# zxuno.net
KiCad netlist of a schematic drawn in EAGLE
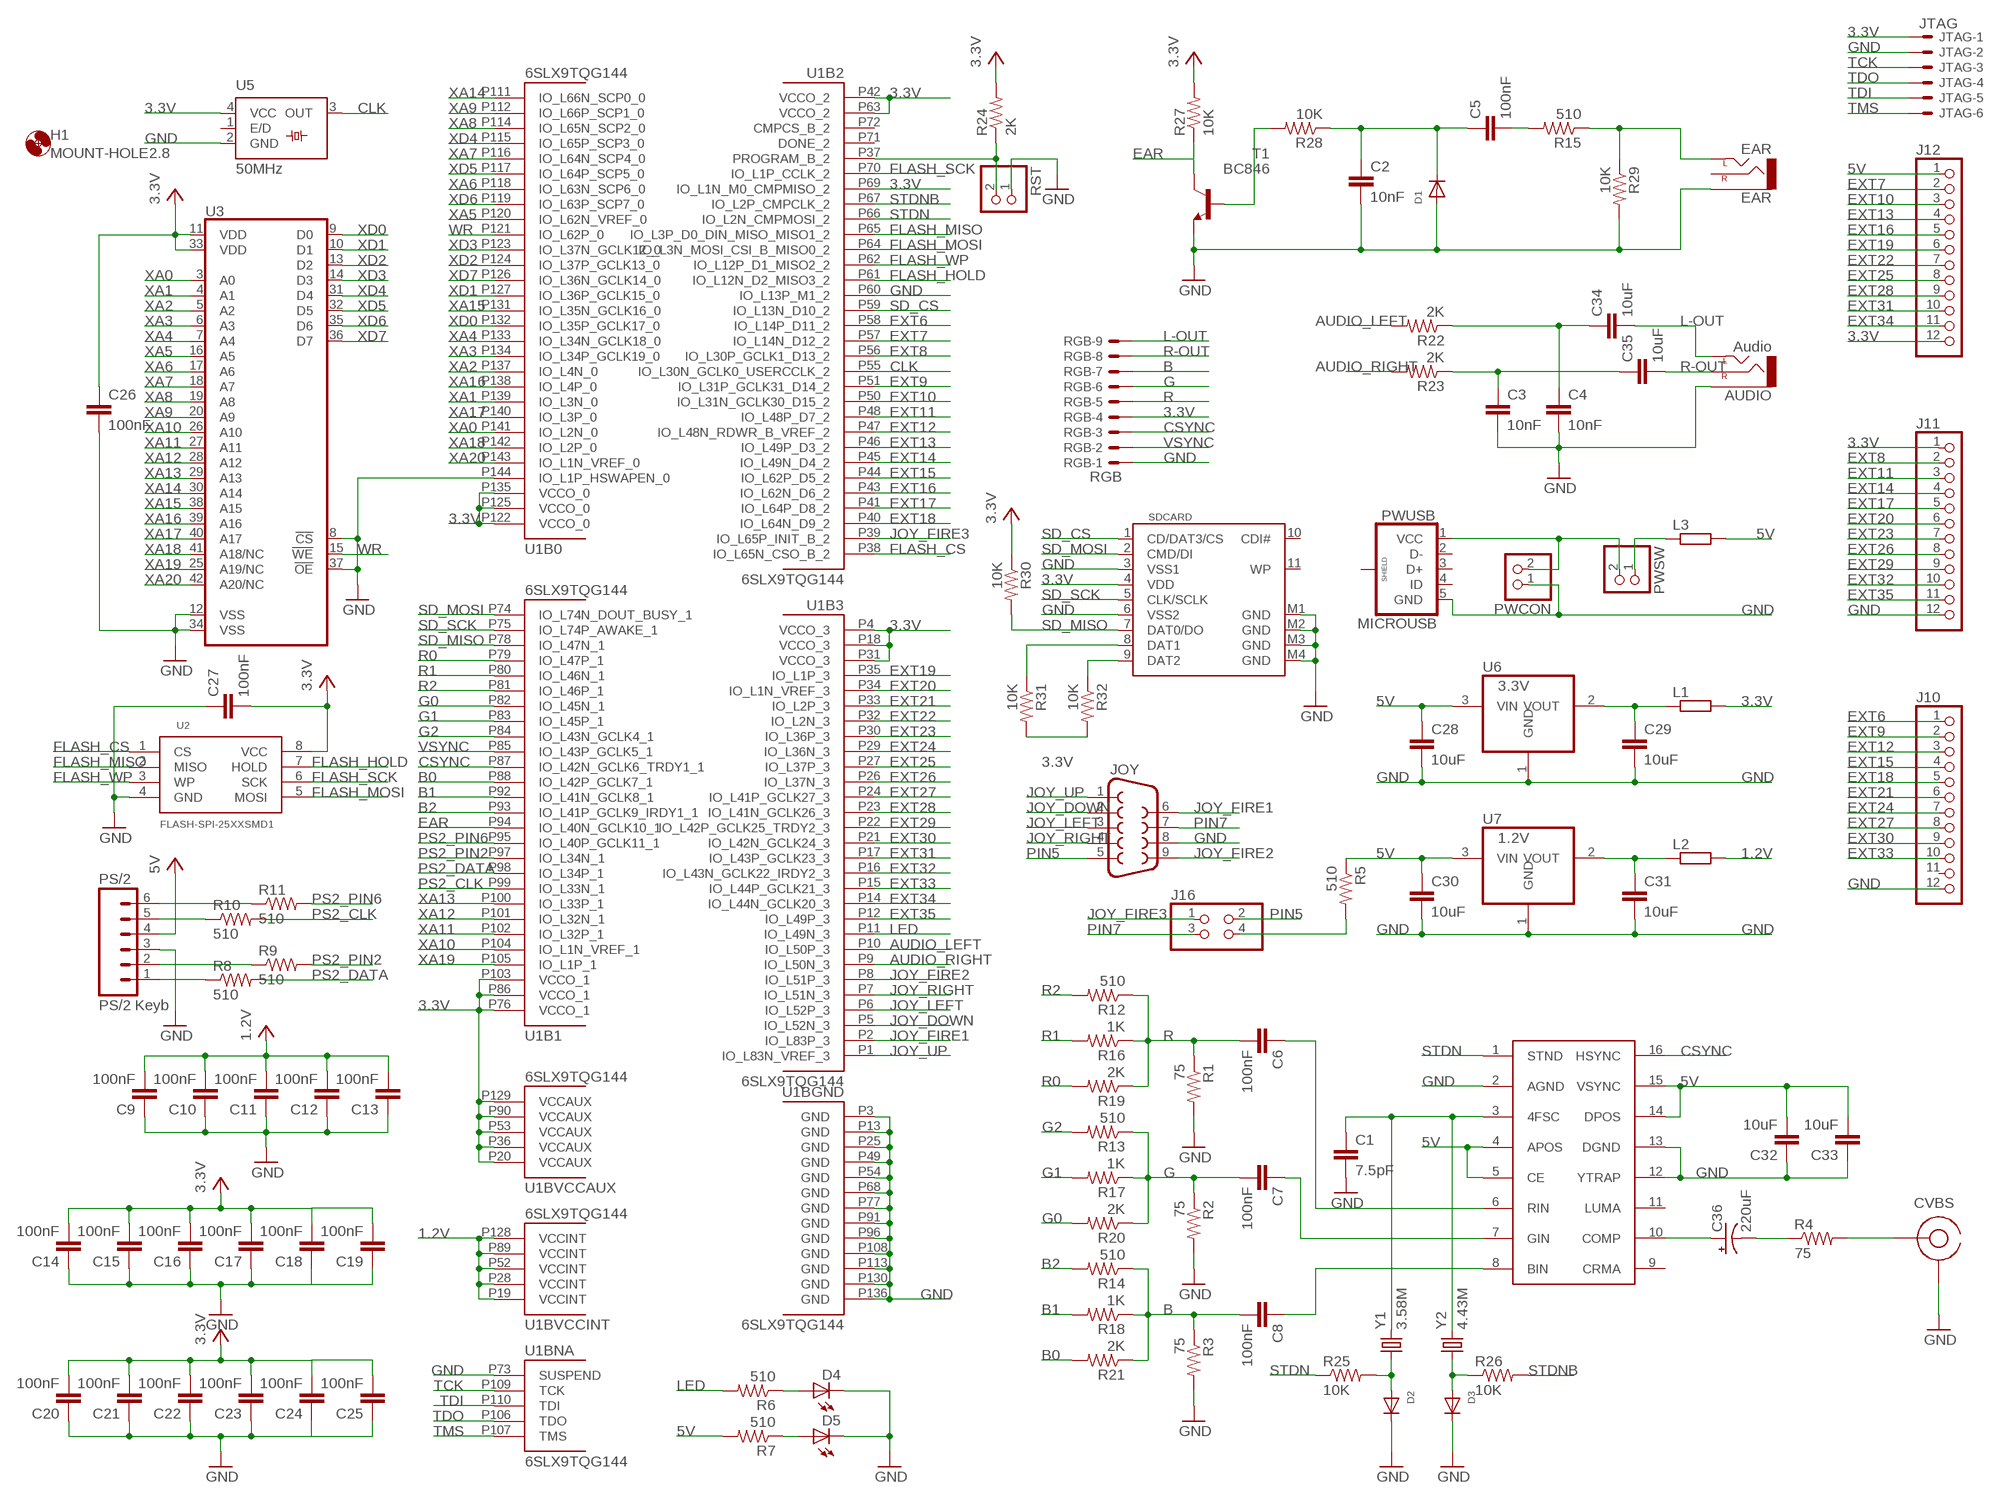
[diagram p0: schematic, sheet 1]

(export (version "E")
  (design (tool "Eeschema 10.0.6"))
  (components
    (comp (ref "AUDIO")
      (value "Audio")
      (footprint "eagle-import:AUDIO-JACK")
      (libsource (lib "eagle-import") (part "AUDIO-JACKPTH"))
    )
    (comp (ref "C1")
      (value "7.5pF")
      (footprint "eagle-import:C0805")
      (libsource (lib "eagle-import") (part "C-EUC0805"))
    )
    (comp (ref "C2")
      (value "10nF")
      (footprint "eagle-import:C0805")
      (libsource (lib "eagle-import") (part "C-EUC0805"))
    )
    (comp (ref "C3")
      (value "10nF")
      (footprint "eagle-import:C0805")
      (libsource (lib "eagle-import") (part "C-EUC0805"))
    )
    (comp (ref "C4")
      (value "10nF")
      (footprint "eagle-import:C0805")
      (libsource (lib "eagle-import") (part "C-EUC0805"))
    )
    (comp (ref "C5")
      (value "100nF")
      (footprint "eagle-import:C0603")
      (libsource (lib "eagle-import") (part "C-EUC0603"))
    )
    (comp (ref "C6")
      (value "100nF")
      (footprint "eagle-import:C0603")
      (libsource (lib "eagle-import") (part "C-EUC0603"))
    )
    (comp (ref "C7")
      (value "100nF")
      (footprint "eagle-import:C0603")
      (libsource (lib "eagle-import") (part "C-EUC0603"))
    )
    (comp (ref "C8")
      (value "100nF")
      (footprint "eagle-import:C0603")
      (libsource (lib "eagle-import") (part "C-EUC0603"))
    )
    (comp (ref "C9")
      (value "100nF")
      (footprint "eagle-import:C0603")
      (libsource (lib "eagle-import") (part "C-EUC0603"))
    )
    (comp (ref "C10")
      (value "100nF")
      (footprint "eagle-import:C0603")
      (libsource (lib "eagle-import") (part "C-EUC0603"))
    )
    (comp (ref "C11")
      (value "100nF")
      (footprint "eagle-import:C0603")
      (libsource (lib "eagle-import") (part "C-EUC0603"))
    )
    (comp (ref "C12")
      (value "100nF")
      (footprint "eagle-import:C0603")
      (libsource (lib "eagle-import") (part "C-EUC0603"))
    )
    (comp (ref "C13")
      (value "100nF")
      (footprint "eagle-import:C0603")
      (libsource (lib "eagle-import") (part "C-EUC0603"))
    )
    (comp (ref "C14")
      (value "100nF")
      (footprint "eagle-import:C0603")
      (libsource (lib "eagle-import") (part "C-EUC0603"))
    )
    (comp (ref "C15")
      (value "100nF")
      (footprint "eagle-import:C0603")
      (libsource (lib "eagle-import") (part "C-EUC0603"))
    )
    (comp (ref "C16")
      (value "100nF")
      (footprint "eagle-import:C0603")
      (libsource (lib "eagle-import") (part "C-EUC0603"))
    )
    (comp (ref "C17")
      (value "100nF")
      (footprint "eagle-import:C0603")
      (libsource (lib "eagle-import") (part "C-EUC0603"))
    )
    (comp (ref "C18")
      (value "100nF")
      (footprint "eagle-import:C0603")
      (libsource (lib "eagle-import") (part "C-EUC0603"))
    )
    (comp (ref "C19")
      (value "100nF")
      (footprint "eagle-import:C0603")
      (libsource (lib "eagle-import") (part "C-EUC0603"))
    )
    (comp (ref "C20")
      (value "100nF")
      (footprint "eagle-import:C0603")
      (libsource (lib "eagle-import") (part "C-EUC0603"))
    )
    (comp (ref "C21")
      (value "100nF")
      (footprint "eagle-import:C0603")
      (libsource (lib "eagle-import") (part "C-EUC0603"))
    )
    (comp (ref "C22")
      (value "100nF")
      (footprint "eagle-import:C0603")
      (libsource (lib "eagle-import") (part "C-EUC0603"))
    )
    (comp (ref "C23")
      (value "100nF")
      (footprint "eagle-import:C0603")
      (libsource (lib "eagle-import") (part "C-EUC0603"))
    )
    (comp (ref "C24")
      (value "100nF")
      (footprint "eagle-import:C0603")
      (libsource (lib "eagle-import") (part "C-EUC0603"))
    )
    (comp (ref "C25")
      (value "100nF")
      (footprint "eagle-import:C0603")
      (libsource (lib "eagle-import") (part "C-EUC0603"))
    )
    (comp (ref "C26")
      (value "100nF")
      (footprint "eagle-import:C0603")
      (libsource (lib "eagle-import") (part "C-EUC0603"))
    )
    (comp (ref "C27")
      (value "100nF")
      (footprint "eagle-import:C0603")
      (libsource (lib "eagle-import") (part "C-EUC0603"))
    )
    (comp (ref "C28")
      (value "10uF")
      (footprint "eagle-import:C0805")
      (libsource (lib "eagle-import") (part "C-EUC0805"))
    )
    (comp (ref "C29")
      (value "10uF")
      (footprint "eagle-import:C0805")
      (libsource (lib "eagle-import") (part "C-EUC0805"))
    )
    (comp (ref "C30")
      (value "10uF")
      (footprint "eagle-import:C0805")
      (libsource (lib "eagle-import") (part "C-EUC0805"))
    )
    (comp (ref "C31")
      (value "10uF")
      (footprint "eagle-import:C0805")
      (libsource (lib "eagle-import") (part "C-EUC0805"))
    )
    (comp (ref "C32")
      (value "10uF")
      (footprint "eagle-import:C0805")
      (libsource (lib "eagle-import") (part "C-EUC0805"))
    )
    (comp (ref "C33")
      (value "10uF")
      (footprint "eagle-import:C0805")
      (libsource (lib "eagle-import") (part "C-EUC0805"))
    )
    (comp (ref "C34")
      (value "10uF")
      (footprint "eagle-import:C0805")
      (libsource (lib "eagle-import") (part "C-EUC0805"))
    )
    (comp (ref "C35")
      (value "10uF")
      (footprint "eagle-import:C0805")
      (libsource (lib "eagle-import") (part "C-EUC0805"))
    )
    (comp (ref "C36")
      (value "220uF")
      (footprint "eagle-import:153CLV-0605")
      (libsource (lib "eagle-import") (part "CPOL-US153CLV-0605"))
    )
    (comp (ref "CVBS")
      (value "RCA")
      (footprint "eagle-import:RCA")
      (libsource (lib "eagle-import") (part "RCA"))
    )
    (comp (ref "D1")
      (value "DIODESOD-323F")
      (footprint "eagle-import:SOD-323F")
      (libsource (lib "eagle-import") (part "DIODESOD-323F"))
    )
    (comp (ref "D2")
      (value "DIODESOD-323F")
      (footprint "eagle-import:SOD-323F")
      (libsource (lib "eagle-import") (part "DIODESOD-323F"))
    )
    (comp (ref "D3")
      (value "DIODESOD-323F")
      (footprint "eagle-import:SOD-323F")
      (libsource (lib "eagle-import") (part "DIODESOD-323F"))
    )
    (comp (ref "D4")
      (value "LEDCHIP-LED0805")
      (footprint "eagle-import:CHIP-LED0805")
      (libsource (lib "eagle-import") (part "LEDCHIP-LED0805"))
    )
    (comp (ref "D5")
      (value "LEDCHIP-LED0805")
      (footprint "eagle-import:CHIP-LED0805")
      (libsource (lib "eagle-import") (part "LEDCHIP-LED0805"))
    )
    (comp (ref "EAR")
      (value "EAR")
      (footprint "eagle-import:AUDIO-JACK")
      (libsource (lib "eagle-import") (part "AUDIO-JACKPTH"))
    )
    (comp (ref "H1")
      (value "MOUNT-HOLE2.8")
      (footprint "eagle-import:2,8")
      (libsource (lib "eagle-import") (part "MOUNT-HOLE2.8"))
    )
    (comp (ref "J10")
      (value "PINHD-1X12")
      (footprint "eagle-import:1X12")
      (libsource (lib "eagle-import") (part "PINHD-1X12"))
    )
    (comp (ref "J11")
      (value "PINHD-1X12")
      (footprint "eagle-import:1X12")
      (libsource (lib "eagle-import") (part "PINHD-1X12"))
    )
    (comp (ref "J12")
      (value "PINHD-1X12")
      (footprint "eagle-import:1X12")
      (libsource (lib "eagle-import") (part "PINHD-1X12"))
    )
    (comp (ref "J16")
      (value "PINHD-2X2")
      (footprint "eagle-import:2X02")
      (libsource (lib "eagle-import") (part "PINHD-2X2"))
    )
    (comp (ref "JOY")
      (value "DB9MALE")
      (footprint "eagle-import:DB9_MALE")
      (libsource (lib "eagle-import") (part "DB9MALE"))
    )
    (comp (ref "JTAG")
      (value "JTAG")
      (footprint "eagle-import:53047-06")
      (fields (field (name "MPN") "53047-0610-C"))
      (libsource (lib "eagle-import") (part "53?-06047"))
    )
    (comp (ref "L1")
      (value "R-EU_M0805")
      (footprint "eagle-import:M0805")
      (libsource (lib "eagle-import") (part "R-EU_M0805"))
    )
    (comp (ref "L2")
      (value "R-EU_M0805")
      (footprint "eagle-import:M0805")
      (libsource (lib "eagle-import") (part "R-EU_M0805"))
    )
    (comp (ref "L3")
      (value "R-EU_M0805")
      (footprint "eagle-import:M0805")
      (libsource (lib "eagle-import") (part "R-EU_M0805"))
    )
    (comp (ref "PS/2")
      (value "PS/2 Keyb")
      (footprint "eagle-import:DINC_MIN_TM_6_1PRIMARY")
      (libsource (lib "eagle-import") (part "DINC_MIN_TM_6_1"))
    )
    (comp (ref "PWCON")
      (value "PINHD-1X2")
      (footprint "eagle-import:1X02")
      (libsource (lib "eagle-import") (part "PINHD-1X2"))
    )
    (comp (ref "PWSW")
      (value "PINHD-1X2")
      (footprint "eagle-import:1X02")
      (libsource (lib "eagle-import") (part "PINHD-1X2"))
    )
    (comp (ref "PWUSB")
      (value "MICROUSB")
      (footprint "eagle-import:MICRO_USB_1PRIMARY")
      (libsource (lib "eagle-import") (part "MICROUSB"))
    )
    (comp (ref "R1")
      (value "75")
      (footprint "eagle-import:M0805")
      (libsource (lib "eagle-import") (part "R-US_M0805"))
    )
    (comp (ref "R2")
      (value "75")
      (footprint "eagle-import:M0805")
      (libsource (lib "eagle-import") (part "R-US_M0805"))
    )
    (comp (ref "R3")
      (value "75")
      (footprint "eagle-import:M0805")
      (libsource (lib "eagle-import") (part "R-US_M0805"))
    )
    (comp (ref "R4")
      (value "75")
      (footprint "eagle-import:M0805")
      (libsource (lib "eagle-import") (part "R-US_M0805"))
    )
    (comp (ref "R5")
      (value "510")
      (footprint "eagle-import:M0805")
      (libsource (lib "eagle-import") (part "R-US_M0805"))
    )
    (comp (ref "R6")
      (value "510")
      (footprint "eagle-import:M0805")
      (libsource (lib "eagle-import") (part "R-US_M0805"))
    )
    (comp (ref "R7")
      (value "510")
      (footprint "eagle-import:M0805")
      (libsource (lib "eagle-import") (part "R-US_M0805"))
    )
    (comp (ref "R8")
      (value "510")
      (footprint "eagle-import:M0805")
      (libsource (lib "eagle-import") (part "R-US_M0805"))
    )
    (comp (ref "R9")
      (value "510")
      (footprint "eagle-import:M0805")
      (libsource (lib "eagle-import") (part "R-US_M0805"))
    )
    (comp (ref "R10")
      (value "510")
      (footprint "eagle-import:M0805")
      (libsource (lib "eagle-import") (part "R-US_M0805"))
    )
    (comp (ref "R11")
      (value "510")
      (footprint "eagle-import:M0805")
      (libsource (lib "eagle-import") (part "R-US_M0805"))
    )
    (comp (ref "R12")
      (value "510")
      (footprint "eagle-import:M0805")
      (libsource (lib "eagle-import") (part "R-US_M0805"))
    )
    (comp (ref "R13")
      (value "510")
      (footprint "eagle-import:M0805")
      (libsource (lib "eagle-import") (part "R-US_M0805"))
    )
    (comp (ref "R14")
      (value "510")
      (footprint "eagle-import:M0805")
      (libsource (lib "eagle-import") (part "R-US_M0805"))
    )
    (comp (ref "R15")
      (value "510")
      (footprint "eagle-import:M0805")
      (libsource (lib "eagle-import") (part "R-US_M0805"))
    )
    (comp (ref "R16")
      (value "1K")
      (footprint "eagle-import:M0805")
      (libsource (lib "eagle-import") (part "R-US_M0805"))
    )
    (comp (ref "R17")
      (value "1K")
      (footprint "eagle-import:M0805")
      (libsource (lib "eagle-import") (part "R-US_M0805"))
    )
    (comp (ref "R18")
      (value "1K")
      (footprint "eagle-import:M0805")
      (libsource (lib "eagle-import") (part "R-US_M0805"))
    )
    (comp (ref "R19")
      (value "2K")
      (footprint "eagle-import:M0805")
      (libsource (lib "eagle-import") (part "R-US_M0805"))
    )
    (comp (ref "R20")
      (value "2K")
      (footprint "eagle-import:M0805")
      (libsource (lib "eagle-import") (part "R-US_M0805"))
    )
    (comp (ref "R21")
      (value "2K")
      (footprint "eagle-import:M0805")
      (libsource (lib "eagle-import") (part "R-US_M0805"))
    )
    (comp (ref "R22")
      (value "2K")
      (footprint "eagle-import:M0805")
      (libsource (lib "eagle-import") (part "R-US_M0805"))
    )
    (comp (ref "R23")
      (value "2K")
      (footprint "eagle-import:M0805")
      (libsource (lib "eagle-import") (part "R-US_M0805"))
    )
    (comp (ref "R24")
      (value "2K")
      (footprint "eagle-import:M0805")
      (libsource (lib "eagle-import") (part "R-US_M0805"))
    )
    (comp (ref "R25")
      (value "10K")
      (footprint "eagle-import:M0805")
      (libsource (lib "eagle-import") (part "R-US_M0805"))
    )
    (comp (ref "R26")
      (value "10K")
      (footprint "eagle-import:M0805")
      (libsource (lib "eagle-import") (part "R-US_M0805"))
    )
    (comp (ref "R27")
      (value "10K")
      (footprint "eagle-import:M0805")
      (libsource (lib "eagle-import") (part "R-US_M0805"))
    )
    (comp (ref "R28")
      (value "10K")
      (footprint "eagle-import:M0805")
      (libsource (lib "eagle-import") (part "R-US_M0805"))
    )
    (comp (ref "R29")
      (value "10K")
      (footprint "eagle-import:M0805")
      (libsource (lib "eagle-import") (part "R-US_M0805"))
    )
    (comp (ref "R30")
      (value "10K")
      (footprint "eagle-import:M0805")
      (libsource (lib "eagle-import") (part "R-US_M0805"))
    )
    (comp (ref "R31")
      (value "10K")
      (footprint "eagle-import:M0805")
      (libsource (lib "eagle-import") (part "R-US_M0805"))
    )
    (comp (ref "R32")
      (value "10K")
      (footprint "eagle-import:M0805")
      (libsource (lib "eagle-import") (part "R-US_M0805"))
    )
    (comp (ref "RGB")
      (value "RGB")
      (footprint "eagle-import:53048-09")
      (fields (field (name "MPN") "53048-0910"))
      (libsource (lib "eagle-import") (part "53?-09048"))
    )
    (comp (ref "RST")
      (value "PINHD-1X2")
      (footprint "eagle-import:1X02")
      (libsource (lib "eagle-import") (part "PINHD-1X2"))
    )
    (comp (ref "SDCARD")
      (value "SDCARD")
      (footprint "eagle-import:SDCMF-10915W010")
      (libsource (lib "eagle-import") (part "SDCARD"))
    )
    (comp (ref "T1")
      (value "BC846")
      (footprint "eagle-import:SOT23")
      (libsource (lib "eagle-import") (part "BC846"))
    )
    (comp (ref "U1")
      (value "6SLX9TQG144")
      (footprint "eagle-import:TQ144")
      (libsource (lib "eagle-import") (part "6SLX9TQG144"))
    )
    (comp (ref "U2")
      (value "FLASH-SPI-25XXSMD1")
      (footprint "eagle-import:SO08-EIAJ")
      (libsource (lib "eagle-import") (part "FLASH-SPI-25XXSMD1"))
    )
    (comp (ref "U3")
      (value "ISSI_SRAM_8BIT")
      (footprint "eagle-import:TSOP44-II")
      (libsource (lib "eagle-import") (part "ISSI_SRAM_8BIT"))
    )
    (comp (ref "U4")
      (value "AD724")
      (footprint "eagle-import:SO16W")
      (libsource (lib "eagle-import") (part "AD725"))
    )
    (comp (ref "U5")
      (value "50MHz")
      (footprint "eagle-import:SM_OSC_1PRIMARY")
      (libsource (lib "eagle-import") (part "SM_OSC_1"))
    )
    (comp (ref "U6")
      (value "3.3V")
      (footprint "eagle-import:SOT223")
      (fields (field (name "MPN") "REG1117"))
      (libsource (lib "eagle-import") (part "REG1117"))
    )
    (comp (ref "U7")
      (value "1.2V")
      (footprint "eagle-import:SOT223")
      (fields (field (name "MPN") "REG1117"))
      (libsource (lib "eagle-import") (part "REG1117"))
    )
    (comp (ref "Y1")
      (value "3.58M")
      (footprint "eagle-import:HC49UP")
      (libsource (lib "eagle-import") (part "CRYSTALHC49UP"))
    )
    (comp (ref "Y2")
      (value "4.43M")
      (footprint "eagle-import:HC49UP")
      (libsource (lib "eagle-import") (part "CRYSTALHC49UP"))
    )
  )
  (nets
    (net (code "1") (name "/AUDIO_LEFT") (class "Default")
      (node (ref "R22") (pin "2") (pinfunction "2_2") (pintype "passive"))
      (node (ref "U1") (pin "P10") (pinfunction "IO_L50P_3_P10") (pintype "bidirectional"))
    )
    (net (code "2") (name "/AUDIO_RIGHT") (class "Default")
      (node (ref "R23") (pin "2") (pinfunction "2_2") (pintype "passive"))
      (node (ref "U1") (pin "P9") (pinfunction "IO_L50N_3_P9") (pintype "bidirectional"))
    )
    (net (code "3") (name "/B") (class "Default")
      (node (ref "C8") (pin "2") (pinfunction "2_2") (pintype "passive"))
      (node (ref "R14") (pin "1") (pinfunction "1_1") (pintype "passive"))
      (node (ref "R18") (pin "1") (pinfunction "1_1") (pintype "passive"))
      (node (ref "R21") (pin "1") (pinfunction "1_1") (pintype "passive"))
      (node (ref "R3") (pin "1") (pinfunction "1_1") (pintype "passive"))
      (node (ref "RGB") (pin "7") (pinfunction "S_7") (pintype "passive"))
    )
    (net (code "4") (name "/B0") (class "Default")
      (node (ref "R21") (pin "2") (pinfunction "2_2") (pintype "passive"))
      (node (ref "U1") (pin "P88") (pinfunction "IO_L42P_GCLK7_1_P88") (pintype "bidirectional"))
    )
    (net (code "5") (name "/B1") (class "Default")
      (node (ref "R18") (pin "2") (pinfunction "2_2") (pintype "passive"))
      (node (ref "U1") (pin "P92") (pinfunction "IO_L41N_GCLK8_1_P92") (pintype "bidirectional"))
    )
    (net (code "6") (name "/B2") (class "Default")
      (node (ref "R14") (pin "2") (pinfunction "2_2") (pintype "passive"))
      (node (ref "U1") (pin "P93") (pinfunction "IO_L41P_GCLK9_IRDY1_1_P93") (pintype "bidirectional"))
    )
    (net (code "7") (name "/CLK") (class "Default")
      (node (ref "U1") (pin "P55") (pinfunction "IO_L30N_GCLK0_USERCCLK_2_P55") (pintype "bidirectional"))
      (node (ref "U5") (pin "3") (pinfunction "OUT_3") (pintype "output"))
    )
    (net (code "8") (name "/CSYNC") (class "Default")
      (node (ref "RGB") (pin "3") (pinfunction "S_3") (pintype "passive"))
      (node (ref "U1") (pin "P87") (pinfunction "IO_L42N_GCLK6_TRDY1_1_P87") (pintype "bidirectional"))
      (node (ref "U4") (pin "16") (pinfunction "HSYNC_16") (pintype "bidirectional"))
    )
    (net (code "9") (name "/EAR") (class "Default")
      (node (ref "R27") (pin "1") (pinfunction "1_1") (pintype "passive"))
      (node (ref "T1") (pin "3") (pinfunction "C_3") (pintype "passive"))
      (node (ref "U1") (pin "P94") (pinfunction "IO_L40N_GCLK10_1_P94") (pintype "bidirectional"))
    )
    (net (code "10") (name "/EXT6") (class "Default")
      (node (ref "J10") (pin "1") (pinfunction "1_1") (pintype "passive"))
      (node (ref "U1") (pin "P58") (pinfunction "IO_L14P_D11_2_P58") (pintype "bidirectional"))
    )
    (net (code "11") (name "/EXT7") (class "Default")
      (node (ref "J12") (pin "2") (pinfunction "2_2") (pintype "passive"))
      (node (ref "U1") (pin "P57") (pinfunction "IO_L14N_D12_2_P57") (pintype "bidirectional"))
    )
    (net (code "12") (name "/EXT8") (class "Default")
      (node (ref "J11") (pin "2") (pinfunction "2_2") (pintype "passive"))
      (node (ref "U1") (pin "P56") (pinfunction "IO_L30P_GCLK1_D13_2_P56") (pintype "bidirectional"))
    )
    (net (code "13") (name "/EXT9") (class "Default")
      (node (ref "J10") (pin "2") (pinfunction "2_2") (pintype "passive"))
      (node (ref "U1") (pin "P51") (pinfunction "IO_L31P_GCLK31_D14_2_P51") (pintype "bidirectional"))
    )
    (net (code "14") (name "/EXT10") (class "Default")
      (node (ref "J12") (pin "3") (pinfunction "3_3") (pintype "passive"))
      (node (ref "U1") (pin "P50") (pinfunction "IO_L31N_GCLK30_D15_2_P50") (pintype "bidirectional"))
    )
    (net (code "15") (name "/EXT11") (class "Default")
      (node (ref "J11") (pin "3") (pinfunction "3_3") (pintype "passive"))
      (node (ref "U1") (pin "P48") (pinfunction "IO_L48P_D7_2_P48") (pintype "bidirectional"))
    )
    (net (code "16") (name "/EXT12") (class "Default")
      (node (ref "J10") (pin "3") (pinfunction "3_3") (pintype "passive"))
      (node (ref "U1") (pin "P47") (pinfunction "IO_L48N_RDWR_B_VREF_2_P47") (pintype "bidirectional"))
    )
    (net (code "17") (name "/EXT13") (class "Default")
      (node (ref "J12") (pin "4") (pinfunction "4_4") (pintype "passive"))
      (node (ref "U1") (pin "P46") (pinfunction "IO_L49P_D3_2_P46") (pintype "bidirectional"))
    )
    (net (code "18") (name "/EXT14") (class "Default")
      (node (ref "J11") (pin "4") (pinfunction "4_4") (pintype "passive"))
      (node (ref "U1") (pin "P45") (pinfunction "IO_L49N_D4_2_P45") (pintype "bidirectional"))
    )
    (net (code "19") (name "/EXT15") (class "Default")
      (node (ref "J10") (pin "4") (pinfunction "4_4") (pintype "passive"))
      (node (ref "U1") (pin "P44") (pinfunction "IO_L62P_D5_2_P44") (pintype "bidirectional"))
    )
    (net (code "20") (name "/EXT16") (class "Default")
      (node (ref "J12") (pin "5") (pinfunction "5_5") (pintype "passive"))
      (node (ref "U1") (pin "P43") (pinfunction "IO_L62N_D6_2_P43") (pintype "bidirectional"))
    )
    (net (code "21") (name "/EXT17") (class "Default")
      (node (ref "J11") (pin "5") (pinfunction "5_5") (pintype "passive"))
      (node (ref "U1") (pin "P41") (pinfunction "IO_L64P_D8_2_P41") (pintype "bidirectional"))
    )
    (net (code "22") (name "/EXT18") (class "Default")
      (node (ref "J10") (pin "5") (pinfunction "5_5") (pintype "passive"))
      (node (ref "U1") (pin "P40") (pinfunction "IO_L64N_D9_2_P40") (pintype "bidirectional"))
    )
    (net (code "23") (name "/EXT19") (class "Default")
      (node (ref "J12") (pin "6") (pinfunction "6_6") (pintype "passive"))
      (node (ref "U1") (pin "P35") (pinfunction "IO_L1P_3_P35") (pintype "bidirectional"))
    )
    (net (code "24") (name "/EXT20") (class "Default")
      (node (ref "J11") (pin "6") (pinfunction "6_6") (pintype "passive"))
      (node (ref "U1") (pin "P34") (pinfunction "IO_L1N_VREF_3_P34") (pintype "bidirectional"))
    )
    (net (code "25") (name "/EXT21") (class "Default")
      (node (ref "J10") (pin "6") (pinfunction "6_6") (pintype "passive"))
      (node (ref "U1") (pin "P33") (pinfunction "IO_L2P_3_P33") (pintype "bidirectional"))
    )
    (net (code "26") (name "/EXT22") (class "Default")
      (node (ref "J12") (pin "7") (pinfunction "7_7") (pintype "passive"))
      (node (ref "U1") (pin "P32") (pinfunction "IO_L2N_3_P32") (pintype "bidirectional"))
    )
    (net (code "27") (name "/EXT23") (class "Default")
      (node (ref "J11") (pin "7") (pinfunction "7_7") (pintype "passive"))
      (node (ref "U1") (pin "P30") (pinfunction "IO_L36P_3_P30") (pintype "bidirectional"))
    )
    (net (code "28") (name "/EXT24") (class "Default")
      (node (ref "J10") (pin "7") (pinfunction "7_7") (pintype "passive"))
      (node (ref "U1") (pin "P29") (pinfunction "IO_L36N_3_P29") (pintype "bidirectional"))
    )
    (net (code "29") (name "/EXT25") (class "Default")
      (node (ref "J12") (pin "8") (pinfunction "8_8") (pintype "passive"))
      (node (ref "U1") (pin "P27") (pinfunction "IO_L37P_3_P27") (pintype "bidirectional"))
    )
    (net (code "30") (name "/EXT26") (class "Default")
      (node (ref "J11") (pin "8") (pinfunction "8_8") (pintype "passive"))
      (node (ref "U1") (pin "P26") (pinfunction "IO_L37N_3_P26") (pintype "bidirectional"))
    )
    (net (code "31") (name "/EXT27") (class "Default")
      (node (ref "J10") (pin "8") (pinfunction "8_8") (pintype "passive"))
      (node (ref "U1") (pin "P24") (pinfunction "IO_L41P_GCLK27_3_P24") (pintype "bidirectional"))
    )
    (net (code "32") (name "/EXT28") (class "Default")
      (node (ref "J12") (pin "9") (pinfunction "9_9") (pintype "passive"))
      (node (ref "U1") (pin "P23") (pinfunction "IO_L41N_GCLK26_3_P23") (pintype "bidirectional"))
    )
    (net (code "33") (name "/EXT29") (class "Default")
      (node (ref "J11") (pin "9") (pinfunction "9_9") (pintype "passive"))
      (node (ref "U1") (pin "P22") (pinfunction "IO_L42P_GCLK25_TRDY2_3_P22") (pintype "bidirectional"))
    )
    (net (code "34") (name "/EXT30") (class "Default")
      (node (ref "J10") (pin "9") (pinfunction "9_9") (pintype "passive"))
      (node (ref "U1") (pin "P21") (pinfunction "IO_L42N_GCLK24_3_P21") (pintype "bidirectional"))
    )
    (net (code "35") (name "/EXT31") (class "Default")
      (node (ref "J12") (pin "10") (pinfunction "10_10") (pintype "passive"))
      (node (ref "U1") (pin "P17") (pinfunction "IO_L43P_GCLK23_3_P17") (pintype "bidirectional"))
    )
    (net (code "36") (name "/EXT32") (class "Default")
      (node (ref "J11") (pin "10") (pinfunction "10_10") (pintype "passive"))
      (node (ref "U1") (pin "P16") (pinfunction "IO_L43N_GCLK22_IRDY2_3_P16") (pintype "bidirectional"))
    )
    (net (code "37") (name "/EXT33") (class "Default")
      (node (ref "J10") (pin "10") (pinfunction "10_10") (pintype "passive"))
      (node (ref "U1") (pin "P15") (pinfunction "IO_L44P_GCLK21_3_P15") (pintype "bidirectional"))
    )
    (net (code "38") (name "/EXT34") (class "Default")
      (node (ref "J12") (pin "11") (pinfunction "11_11") (pintype "passive"))
      (node (ref "U1") (pin "P14") (pinfunction "IO_L44N_GCLK20_3_P14") (pintype "bidirectional"))
    )
    (net (code "39") (name "/EXT35") (class "Default")
      (node (ref "J11") (pin "11") (pinfunction "11_11") (pintype "passive"))
      (node (ref "U1") (pin "P12") (pinfunction "IO_L49P_3_P12") (pintype "bidirectional"))
    )
    (net (code "40") (name "/FLASH_CS") (class "Default")
      (node (ref "U1") (pin "P38") (pinfunction "IO_L65N_CSO_B_2_P38") (pintype "bidirectional"))
      (node (ref "U2") (pin "1") (pinfunction "CS_1") (pintype "bidirectional"))
    )
    (net (code "41") (name "/FLASH_HOLD") (class "Default")
      (node (ref "U1") (pin "P61") (pinfunction "IO_L12N_D2_MISO3_2_P61") (pintype "bidirectional"))
      (node (ref "U2") (pin "7") (pinfunction "HOLD_7") (pintype "bidirectional"))
    )
    (net (code "42") (name "/FLASH_MISO") (class "Default")
      (node (ref "U1") (pin "P65") (pinfunction "IO_L3P_D0_DIN_MISO_MISO1_2_P65") (pintype "bidirectional"))
      (node (ref "U2") (pin "2") (pinfunction "MISO_2") (pintype "bidirectional"))
    )
    (net (code "43") (name "/FLASH_MOSI") (class "Default")
      (node (ref "U1") (pin "P64") (pinfunction "IO_L3N_MOSI_CSI_B_MISO0_2_P64") (pintype "bidirectional"))
      (node (ref "U2") (pin "5") (pinfunction "MOSI_5") (pintype "bidirectional"))
    )
    (net (code "44") (name "/FLASH_SCK") (class "Default")
      (node (ref "U1") (pin "P70") (pinfunction "IO_L1P_CCLK_2_P70") (pintype "bidirectional"))
      (node (ref "U2") (pin "6") (pinfunction "SCK_6") (pintype "bidirectional"))
    )
    (net (code "45") (name "/FLASH_WP") (class "Default")
      (node (ref "U1") (pin "P62") (pinfunction "IO_L12P_D1_MISO2_2_P62") (pintype "bidirectional"))
      (node (ref "U2") (pin "3") (pinfunction "WP_3") (pintype "bidirectional"))
    )
    (net (code "46") (name "/G") (class "Default")
      (node (ref "C7") (pin "2") (pinfunction "2_2") (pintype "passive"))
      (node (ref "R13") (pin "1") (pinfunction "1_1") (pintype "passive"))
      (node (ref "R17") (pin "1") (pinfunction "1_1") (pintype "passive"))
      (node (ref "R2") (pin "1") (pinfunction "1_1") (pintype "passive"))
      (node (ref "R20") (pin "1") (pinfunction "1_1") (pintype "passive"))
      (node (ref "RGB") (pin "6") (pinfunction "S_6") (pintype "passive"))
    )
    (net (code "47") (name "/G0") (class "Default")
      (node (ref "R20") (pin "2") (pinfunction "2_2") (pintype "passive"))
      (node (ref "U1") (pin "P82") (pinfunction "IO_L45N_1_P82") (pintype "bidirectional"))
    )
    (net (code "48") (name "/G1") (class "Default")
      (node (ref "R17") (pin "2") (pinfunction "2_2") (pintype "passive"))
      (node (ref "U1") (pin "P83") (pinfunction "IO_L45P_1_P83") (pintype "bidirectional"))
    )
    (net (code "49") (name "/G2") (class "Default")
      (node (ref "R13") (pin "2") (pinfunction "2_2") (pintype "passive"))
      (node (ref "U1") (pin "P84") (pinfunction "IO_L43N_GCLK4_1_P84") (pintype "bidirectional"))
    )
    (net (code "50") (name "/JOY_DOWN") (class "Default")
      (node (ref "JOY") (pin "2") (pinfunction "2_2") (pintype "passive"))
      (node (ref "U1") (pin "P5") (pinfunction "IO_L52N_3_P5") (pintype "bidirectional"))
    )
    (net (code "51") (name "/JOY_FIRE1") (class "Default")
      (node (ref "JOY") (pin "6") (pinfunction "6_6") (pintype "passive"))
      (node (ref "U1") (pin "P2") (pinfunction "IO_L83P_3_P2") (pintype "bidirectional"))
    )
    (net (code "52") (name "/JOY_FIRE2") (class "Default")
      (node (ref "JOY") (pin "9") (pinfunction "9_9") (pintype "passive"))
      (node (ref "U1") (pin "P8") (pinfunction "IO_L51P_3_P8") (pintype "bidirectional"))
    )
    (net (code "53") (name "/JOY_FIRE3") (class "Default")
      (node (ref "J16") (pin "1") (pinfunction "1_1") (pintype "passive"))
      (node (ref "U1") (pin "P39") (pinfunction "IO_L65P_INIT_B_2_P39") (pintype "bidirectional"))
    )
    (net (code "54") (name "/JOY_LEFT") (class "Default")
      (node (ref "JOY") (pin "3") (pinfunction "3_3") (pintype "passive"))
      (node (ref "U1") (pin "P6") (pinfunction "IO_L52P_3_P6") (pintype "bidirectional"))
    )
    (net (code "55") (name "/JOY_RIGHT") (class "Default")
      (node (ref "JOY") (pin "4") (pinfunction "4_4") (pintype "passive"))
      (node (ref "U1") (pin "P7") (pinfunction "IO_L51N_3_P7") (pintype "bidirectional"))
    )
    (net (code "56") (name "/JOY_UP") (class "Default")
      (node (ref "JOY") (pin "1") (pinfunction "1_1") (pintype "passive"))
      (node (ref "U1") (pin "P1") (pinfunction "IO_L83N_VREF_3_P1") (pintype "bidirectional"))
    )
    (net (code "57") (name "/L-OUT") (class "Default")
      (node (ref "AUDIO") (pin "TIP") (pinfunction "LEFT_TIP") (pintype "bidirectional"))
      (node (ref "C34") (pin "2") (pinfunction "2_2") (pintype "passive"))
      (node (ref "RGB") (pin "9") (pinfunction "S_9") (pintype "passive"))
    )
    (net (code "58") (name "/LED") (class "Default")
      (node (ref "R6") (pin "2") (pinfunction "2_2") (pintype "passive"))
      (node (ref "U1") (pin "P11") (pinfunction "IO_L49N_3_P11") (pintype "bidirectional"))
    )
    (net (code "59") (name "/PIN5") (class "Default")
      (node (ref "J16") (pin "2") (pinfunction "2_2") (pintype "passive"))
      (node (ref "JOY") (pin "5") (pinfunction "5_5") (pintype "passive"))
    )
    (net (code "60") (name "/PIN7") (class "Default")
      (node (ref "J16") (pin "3") (pinfunction "3_3") (pintype "passive"))
      (node (ref "JOY") (pin "7") (pinfunction "7_7") (pintype "passive"))
    )
    (net (code "61") (name "/PS2_CLK") (class "Default")
      (node (ref "R10") (pin "2") (pinfunction "2_2") (pintype "passive"))
      (node (ref "U1") (pin "P99") (pinfunction "IO_L33N_1_P99") (pintype "bidirectional"))
    )
    (net (code "62") (name "/PS2_DATA") (class "Default")
      (node (ref "R8") (pin "2") (pinfunction "2_2") (pintype "passive"))
      (node (ref "U1") (pin "P98") (pinfunction "IO_L34P_1_P98") (pintype "bidirectional"))
    )
    (net (code "63") (name "/PS2_PIN2") (class "Default")
      (node (ref "R9") (pin "2") (pinfunction "2_2") (pintype "passive"))
      (node (ref "U1") (pin "P97") (pinfunction "IO_L34N_1_P97") (pintype "bidirectional"))
    )
    (net (code "64") (name "/PS2_PIN6") (class "Default")
      (node (ref "R11") (pin "2") (pinfunction "2_2") (pintype "passive"))
      (node (ref "U1") (pin "P95") (pinfunction "IO_L40P_GCLK11_1_P95") (pintype "bidirectional"))
    )
    (net (code "65") (name "/R") (class "Default")
      (node (ref "C6") (pin "2") (pinfunction "2_2") (pintype "passive"))
      (node (ref "R1") (pin "1") (pinfunction "1_1") (pintype "passive"))
      (node (ref "R12") (pin "1") (pinfunction "1_1") (pintype "passive"))
      (node (ref "R16") (pin "1") (pinfunction "1_1") (pintype "passive"))
      (node (ref "R19") (pin "1") (pinfunction "1_1") (pintype "passive"))
      (node (ref "RGB") (pin "5") (pinfunction "S_5") (pintype "passive"))
    )
    (net (code "66") (name "/R-OUT") (class "Default")
      (node (ref "AUDIO") (pin "RING") (pinfunction "RIGHT_RING") (pintype "bidirectional"))
      (node (ref "C35") (pin "2") (pinfunction "2_2") (pintype "passive"))
      (node (ref "RGB") (pin "8") (pinfunction "S_8") (pintype "passive"))
    )
    (net (code "67") (name "/R0") (class "Default")
      (node (ref "R19") (pin "2") (pinfunction "2_2") (pintype "passive"))
      (node (ref "U1") (pin "P79") (pinfunction "IO_L47P_1_P79") (pintype "bidirectional"))
    )
    (net (code "68") (name "/R1") (class "Default")
      (node (ref "R16") (pin "2") (pinfunction "2_2") (pintype "passive"))
      (node (ref "U1") (pin "P80") (pinfunction "IO_L46N_1_P80") (pintype "bidirectional"))
    )
    (net (code "69") (name "/R2") (class "Default")
      (node (ref "R12") (pin "2") (pinfunction "2_2") (pintype "passive"))
      (node (ref "U1") (pin "P81") (pinfunction "IO_L46P_1_P81") (pintype "bidirectional"))
    )
    (net (code "70") (name "/SD_CS") (class "Default")
      (node (ref "SDCARD") (pin "1") (pinfunction "CD/DAT3/CS_1") (pintype "bidirectional"))
      (node (ref "U1") (pin "P59") (pinfunction "IO_L13N_D10_2_P59") (pintype "bidirectional"))
    )
    (net (code "71") (name "/SD_MISO") (class "Default")
      (node (ref "R30") (pin "2") (pinfunction "2_2") (pintype "passive"))
      (node (ref "SDCARD") (pin "7") (pinfunction "DAT0/DO_7") (pintype "bidirectional"))
      (node (ref "U1") (pin "P78") (pinfunction "IO_L47N_1_P78") (pintype "bidirectional"))
    )
    (net (code "72") (name "/SD_MOSI") (class "Default")
      (node (ref "SDCARD") (pin "2") (pinfunction "CMD/DI_2") (pintype "bidirectional"))
      (node (ref "U1") (pin "P74") (pinfunction "IO_L74N_DOUT_BUSY_1_P74") (pintype "bidirectional"))
    )
    (net (code "73") (name "/SD_SCK") (class "Default")
      (node (ref "SDCARD") (pin "5") (pinfunction "CLK/SCLK_5") (pintype "bidirectional"))
      (node (ref "U1") (pin "P75") (pinfunction "IO_L74P_AWAKE_1_P75") (pintype "bidirectional"))
    )
    (net (code "74") (name "/STDN") (class "Default")
      (node (ref "R25") (pin "1") (pinfunction "1_1") (pintype "passive"))
      (node (ref "U1") (pin "P66") (pinfunction "IO_L2N_CMPMOSI_2_P66") (pintype "bidirectional"))
      (node (ref "U4") (pin "1") (pinfunction "STND_1") (pintype "bidirectional"))
    )
    (net (code "75") (name "/STDNB") (class "Default")
      (node (ref "R26") (pin "2") (pinfunction "2_2") (pintype "passive"))
      (node (ref "U1") (pin "P67") (pinfunction "IO_L2P_CMPCLK_2_P67") (pintype "bidirectional"))
    )
    (net (code "76") (name "/TCK") (class "Default")
      (node (ref "JTAG") (pin "3") (pinfunction "S_3") (pintype "passive"))
      (node (ref "U1") (pin "P109") (pinfunction "TCK_P109") (pintype "input"))
    )
    (net (code "77") (name "/TDI") (class "Default")
      (node (ref "JTAG") (pin "5") (pinfunction "S_5") (pintype "passive"))
      (node (ref "U1") (pin "P110") (pinfunction "TDI_P110") (pintype "input"))
    )
    (net (code "78") (name "/TDO") (class "Default")
      (node (ref "JTAG") (pin "4") (pinfunction "S_4") (pintype "passive"))
      (node (ref "U1") (pin "P106") (pinfunction "TDO_P106") (pintype "output"))
    )
    (net (code "79") (name "/TMS") (class "Default")
      (node (ref "JTAG") (pin "6") (pinfunction "S_6") (pintype "passive"))
      (node (ref "U1") (pin "P107") (pinfunction "TMS_P107") (pintype "input"))
    )
    (net (code "80") (name "/VSYNC") (class "Default")
      (node (ref "RGB") (pin "2") (pinfunction "S_2") (pintype "passive"))
      (node (ref "U1") (pin "P85") (pinfunction "IO_L43P_GCLK5_1_P85") (pintype "bidirectional"))
    )
    (net (code "81") (name "/WR") (class "Default")
      (node (ref "U1") (pin "P121") (pinfunction "IO_L62P_0_P121") (pintype "bidirectional"))
      (node (ref "U3") (pin "15") (pinfunction "~{WE}_15") (pintype "input"))
    )
    (net (code "82") (name "/XA0") (class "Default")
      (node (ref "U1") (pin "P141") (pinfunction "IO_L2N_0_P141") (pintype "bidirectional"))
      (node (ref "U3") (pin "3") (pinfunction "A0_3") (pintype "input"))
    )
    (net (code "83") (name "/XA1") (class "Default")
      (node (ref "U1") (pin "P139") (pinfunction "IO_L3N_0_P139") (pintype "bidirectional"))
      (node (ref "U3") (pin "4") (pinfunction "A1_4") (pintype "input"))
    )
    (net (code "84") (name "/XA2") (class "Default")
      (node (ref "U1") (pin "P137") (pinfunction "IO_L4N_0_P137") (pintype "bidirectional"))
      (node (ref "U3") (pin "5") (pinfunction "A2_5") (pintype "input"))
    )
    (net (code "85") (name "/XA3") (class "Default")
      (node (ref "U1") (pin "P134") (pinfunction "IO_L34P_GCLK19_0_P134") (pintype "bidirectional"))
      (node (ref "U3") (pin "6") (pinfunction "A3_6") (pintype "input"))
    )
    (net (code "86") (name "/XA4") (class "Default")
      (node (ref "U1") (pin "P133") (pinfunction "IO_L34N_GCLK18_0_P133") (pintype "bidirectional"))
      (node (ref "U3") (pin "7") (pinfunction "A4_7") (pintype "input"))
    )
    (net (code "87") (name "/XA5") (class "Default")
      (node (ref "U1") (pin "P120") (pinfunction "IO_L62N_VREF_0_P120") (pintype "bidirectional"))
      (node (ref "U3") (pin "16") (pinfunction "A5_16") (pintype "input"))
    )
    (net (code "88") (name "/XA6") (class "Default")
      (node (ref "U1") (pin "P118") (pinfunction "IO_L63N_SCP6_0_P118") (pintype "bidirectional"))
      (node (ref "U3") (pin "17") (pinfunction "A6_17") (pintype "input"))
    )
    (net (code "89") (name "/XA7") (class "Default")
      (node (ref "U1") (pin "P116") (pinfunction "IO_L64N_SCP4_0_P116") (pintype "bidirectional"))
      (node (ref "U3") (pin "18") (pinfunction "A7_18") (pintype "input"))
    )
    (net (code "90") (name "/XA8") (class "Default")
      (node (ref "U1") (pin "P114") (pinfunction "IO_L65N_SCP2_0_P114") (pintype "bidirectional"))
      (node (ref "U3") (pin "19") (pinfunction "A8_19") (pintype "input"))
    )
    (net (code "91") (name "/XA9") (class "Default")
      (node (ref "U1") (pin "P112") (pinfunction "IO_L66P_SCP1_0_P112") (pintype "bidirectional"))
      (node (ref "U3") (pin "20") (pinfunction "A9_20") (pintype "input"))
    )
    (net (code "92") (name "/XA10") (class "Default")
      (node (ref "U1") (pin "P104") (pinfunction "IO_L1N_VREF_1_P104") (pintype "bidirectional"))
      (node (ref "U3") (pin "26") (pinfunction "A10_26") (pintype "input"))
    )
    (net (code "93") (name "/XA11") (class "Default")
      (node (ref "U1") (pin "P102") (pinfunction "IO_L32P_1_P102") (pintype "bidirectional"))
      (node (ref "U3") (pin "27") (pinfunction "A11_27") (pintype "input"))
    )
    (net (code "94") (name "/XA12") (class "Default")
      (node (ref "U1") (pin "P101") (pinfunction "IO_L32N_1_P101") (pintype "bidirectional"))
      (node (ref "U3") (pin "28") (pinfunction "A12_28") (pintype "input"))
    )
    (net (code "95") (name "/XA13") (class "Default")
      (node (ref "U1") (pin "P100") (pinfunction "IO_L33P_1_P100") (pintype "bidirectional"))
      (node (ref "U3") (pin "29") (pinfunction "A13_29") (pintype "input"))
    )
    (net (code "96") (name "/XA14") (class "Default")
      (node (ref "U1") (pin "P111") (pinfunction "IO_L66N_SCP0_0_P111") (pintype "bidirectional"))
      (node (ref "U3") (pin "30") (pinfunction "A14_30") (pintype "input"))
    )
    (net (code "97") (name "/XA15") (class "Default")
      (node (ref "U1") (pin "P131") (pinfunction "IO_L35N_GCLK16_0_P131") (pintype "bidirectional"))
      (node (ref "U3") (pin "38") (pinfunction "A15_38") (pintype "input"))
    )
    (net (code "98") (name "/XA16") (class "Default")
      (node (ref "U1") (pin "P138") (pinfunction "IO_L4P_0_P138") (pintype "bidirectional"))
      (node (ref "U3") (pin "39") (pinfunction "A16_39") (pintype "input"))
    )
    (net (code "99") (name "/XA17") (class "Default")
      (node (ref "U1") (pin "P140") (pinfunction "IO_L3P_0_P140") (pintype "bidirectional"))
      (node (ref "U3") (pin "40") (pinfunction "A17_40") (pintype "input"))
    )
    (net (code "100") (name "/XA18") (class "Default")
      (node (ref "U1") (pin "P142") (pinfunction "IO_L2P_0_P142") (pintype "bidirectional"))
      (node (ref "U3") (pin "41") (pinfunction "A18/NC_41") (pintype "input"))
    )
    (net (code "101") (name "/XA19") (class "Default")
      (node (ref "U1") (pin "P105") (pinfunction "IO_L1P_1_P105") (pintype "bidirectional"))
      (node (ref "U3") (pin "25") (pinfunction "A19/NC_25") (pintype "input"))
    )
    (net (code "102") (name "/XA20") (class "Default")
      (node (ref "U1") (pin "P143") (pinfunction "IO_L1N_VREF_0_P143") (pintype "bidirectional"))
      (node (ref "U3") (pin "42") (pinfunction "A20/NC_42") (pintype "input"))
    )
    (net (code "103") (name "/XD0") (class "Default")
      (node (ref "U1") (pin "P132") (pinfunction "IO_L35P_GCLK17_0_P132") (pintype "bidirectional"))
      (node (ref "U3") (pin "9") (pinfunction "D0_9") (pintype "bidirectional"))
    )
    (net (code "104") (name "/XD1") (class "Default")
      (node (ref "U1") (pin "P127") (pinfunction "IO_L36P_GCLK15_0_P127") (pintype "bidirectional"))
      (node (ref "U3") (pin "10") (pinfunction "D1_10") (pintype "bidirectional"))
    )
    (net (code "105") (name "/XD2") (class "Default")
      (node (ref "U1") (pin "P124") (pinfunction "IO_L37P_GCLK13_0_P124") (pintype "bidirectional"))
      (node (ref "U3") (pin "13") (pinfunction "D2_13") (pintype "bidirectional"))
    )
    (net (code "106") (name "/XD3") (class "Default")
      (node (ref "U1") (pin "P123") (pinfunction "IO_L37N_GCLK12_0_P123") (pintype "bidirectional"))
      (node (ref "U3") (pin "14") (pinfunction "D3_14") (pintype "bidirectional"))
    )
    (net (code "107") (name "/XD4") (class "Default")
      (node (ref "U1") (pin "P115") (pinfunction "IO_L65P_SCP3_0_P115") (pintype "bidirectional"))
      (node (ref "U3") (pin "31") (pinfunction "D4_31") (pintype "bidirectional"))
    )
    (net (code "108") (name "/XD5") (class "Default")
      (node (ref "U1") (pin "P117") (pinfunction "IO_L64P_SCP5_0_P117") (pintype "bidirectional"))
      (node (ref "U3") (pin "32") (pinfunction "D5_32") (pintype "bidirectional"))
    )
    (net (code "109") (name "/XD6") (class "Default")
      (node (ref "U1") (pin "P119") (pinfunction "IO_L63P_SCP7_0_P119") (pintype "bidirectional"))
      (node (ref "U3") (pin "35") (pinfunction "D6_35") (pintype "bidirectional"))
    )
    (net (code "110") (name "/XD7") (class "Default")
      (node (ref "U1") (pin "P126") (pinfunction "IO_L36N_GCLK14_0_P126") (pintype "bidirectional"))
      (node (ref "U3") (pin "36") (pinfunction "D7_36") (pintype "bidirectional"))
    )
    (net (code "111") (name "1.2V") (class "Default")
      (node (ref "C10") (pin "2") (pinfunction "2_2") (pintype "passive"))
      (node (ref "C11") (pin "2") (pinfunction "2_2") (pintype "passive"))
      (node (ref "C12") (pin "2") (pinfunction "2_2") (pintype "passive"))
      (node (ref "C13") (pin "2") (pinfunction "2_2") (pintype "passive"))
      (node (ref "C9") (pin "2") (pinfunction "2_2") (pintype "passive"))
      (node (ref "L2") (pin "2") (pinfunction "2_2") (pintype "passive"))
      (node (ref "U1") (pin "P128") (pinfunction "VCCINT_P128") (pintype "input"))
      (node (ref "U1") (pin "P19") (pinfunction "VCCINT_P19") (pintype "input"))
      (node (ref "U1") (pin "P28") (pinfunction "VCCINT_P28") (pintype "input"))
      (node (ref "U1") (pin "P52") (pinfunction "VCCINT_P52") (pintype "input"))
      (node (ref "U1") (pin "P89") (pinfunction "VCCINT_P89") (pintype "input"))
    )
    (net (code "112") (name "3.3V") (class "Default")
      (node (ref "C14") (pin "2") (pinfunction "2_2") (pintype "passive"))
      (node (ref "C15") (pin "2") (pinfunction "2_2") (pintype "passive"))
      (node (ref "C16") (pin "2") (pinfunction "2_2") (pintype "passive"))
      (node (ref "C17") (pin "2") (pinfunction "2_2") (pintype "passive"))
      (node (ref "C18") (pin "2") (pinfunction "2_2") (pintype "passive"))
      (node (ref "C19") (pin "2") (pinfunction "2_2") (pintype "passive"))
      (node (ref "C20") (pin "2") (pinfunction "2_2") (pintype "passive"))
      (node (ref "C21") (pin "2") (pinfunction "2_2") (pintype "passive"))
      (node (ref "C22") (pin "2") (pinfunction "2_2") (pintype "passive"))
      (node (ref "C23") (pin "2") (pinfunction "2_2") (pintype "passive"))
      (node (ref "C24") (pin "2") (pinfunction "2_2") (pintype "passive"))
      (node (ref "C25") (pin "2") (pinfunction "2_2") (pintype "passive"))
      (node (ref "C26") (pin "1") (pinfunction "1_1") (pintype "passive"))
      (node (ref "C27") (pin "2") (pinfunction "2_2") (pintype "passive"))
      (node (ref "J11") (pin "1") (pinfunction "1_1") (pintype "passive"))
      (node (ref "J12") (pin "12") (pinfunction "12_12") (pintype "passive"))
      (node (ref "JTAG") (pin "1") (pinfunction "S_1") (pintype "passive"))
      (node (ref "L1") (pin "2") (pinfunction "2_2") (pintype "passive"))
      (node (ref "R24") (pin "2") (pinfunction "2_2") (pintype "passive"))
      (node (ref "R27") (pin "2") (pinfunction "2_2") (pintype "passive"))
      (node (ref "R30") (pin "1") (pinfunction "1_1") (pintype "passive"))
      (node (ref "R31") (pin "2") (pinfunction "2_2") (pintype "passive"))
      (node (ref "R32") (pin "2") (pinfunction "2_2") (pintype "passive"))
      (node (ref "RGB") (pin "4") (pinfunction "S_4") (pintype "passive"))
      (node (ref "SDCARD") (pin "4") (pinfunction "VDD_4") (pintype "power_in"))
      (node (ref "U1") (pin "P103") (pinfunction "VCCO_1_P103") (pintype "input"))
      (node (ref "U1") (pin "P122") (pinfunction "VCCO_0_P122") (pintype "input"))
      (node (ref "U1") (pin "P125") (pinfunction "VCCO_0_P125") (pintype "input"))
      (node (ref "U1") (pin "P129") (pinfunction "VCCAUX_P129") (pintype "input"))
      (node (ref "U1") (pin "P135") (pinfunction "VCCO_0_P135") (pintype "input"))
      (node (ref "U1") (pin "P18") (pinfunction "VCCO_3_P18") (pintype "input"))
      (node (ref "U1") (pin "P20") (pinfunction "VCCAUX_P20") (pintype "input"))
      (node (ref "U1") (pin "P31") (pinfunction "VCCO_3_P31") (pintype "input"))
      (node (ref "U1") (pin "P36") (pinfunction "VCCAUX_P36") (pintype "input"))
      (node (ref "U1") (pin "P4") (pinfunction "VCCO_3_P4") (pintype "input"))
      (node (ref "U1") (pin "P42") (pinfunction "VCCO_2_P42") (pintype "input"))
      (node (ref "U1") (pin "P53") (pinfunction "VCCAUX_P53") (pintype "input"))
      (node (ref "U1") (pin "P63") (pinfunction "VCCO_2_P63") (pintype "input"))
      (node (ref "U1") (pin "P69") (pinfunction "IO_L1N_M0_CMPMISO_2_P69") (pintype "bidirectional"))
      (node (ref "U1") (pin "P76") (pinfunction "VCCO_1_P76") (pintype "input"))
      (node (ref "U1") (pin "P86") (pinfunction "VCCO_1_P86") (pintype "input"))
      (node (ref "U1") (pin "P90") (pinfunction "VCCAUX_P90") (pintype "input"))
      (node (ref "U2") (pin "8") (pinfunction "VCC_8") (pintype "bidirectional"))
      (node (ref "U3") (pin "11") (pinfunction "VDD_11") (pintype "input"))
      (node (ref "U3") (pin "33") (pinfunction "VDD_33") (pintype "input"))
      (node (ref "U5") (pin "4") (pinfunction "VCC_4") (pintype "power_in"))
    )
    (net (code "113") (name "5V") (class "Default")
      (node (ref "C28") (pin "1") (pinfunction "1_1") (pintype "passive"))
      (node (ref "C30") (pin "1") (pinfunction "1_1") (pintype "passive"))
      (node (ref "C32") (pin "2") (pinfunction "2_2") (pintype "passive"))
      (node (ref "C33") (pin "2") (pinfunction "2_2") (pintype "passive"))
      (node (ref "J12") (pin "1") (pinfunction "1_1") (pintype "passive"))
      (node (ref "L3") (pin "2") (pinfunction "2_2") (pintype "passive"))
      (node (ref "PS/2") (pin "4") (pinfunction "4_4") (pintype "passive"))
      (node (ref "R5") (pin "1") (pinfunction "1_1") (pintype "passive"))
      (node (ref "R7") (pin "2") (pinfunction "2_2") (pintype "passive"))
      (node (ref "U4") (pin "14") (pinfunction "DPOS_14") (pintype "bidirectional"))
      (node (ref "U4") (pin "15") (pinfunction "VSYNC_15") (pintype "bidirectional"))
      (node (ref "U4") (pin "4") (pinfunction "APOS_4") (pintype "bidirectional"))
      (node (ref "U4") (pin "5") (pinfunction "CE_5") (pintype "bidirectional"))
      (node (ref "U6") (pin "3") (pinfunction "VIN_3") (pintype "input"))
      (node (ref "U7") (pin "3") (pinfunction "VIN_3") (pintype "input"))
    )
    (net (code "114") (name "GND") (class "Default")
      (node (ref "AUDIO") (pin "SLEEVE") (pinfunction "SLEEVE_SLEEVE") (pintype "bidirectional"))
      (node (ref "C1") (pin "2") (pinfunction "2_2") (pintype "passive"))
      (node (ref "C10") (pin "1") (pinfunction "1_1") (pintype "passive"))
      (node (ref "C11") (pin "1") (pinfunction "1_1") (pintype "passive"))
      (node (ref "C12") (pin "1") (pinfunction "1_1") (pintype "passive"))
      (node (ref "C13") (pin "1") (pinfunction "1_1") (pintype "passive"))
      (node (ref "C14") (pin "1") (pinfunction "1_1") (pintype "passive"))
      (node (ref "C15") (pin "1") (pinfunction "1_1") (pintype "passive"))
      (node (ref "C16") (pin "1") (pinfunction "1_1") (pintype "passive"))
      (node (ref "C17") (pin "1") (pinfunction "1_1") (pintype "passive"))
      (node (ref "C18") (pin "1") (pinfunction "1_1") (pintype "passive"))
      (node (ref "C19") (pin "1") (pinfunction "1_1") (pintype "passive"))
      (node (ref "C2") (pin "2") (pinfunction "2_2") (pintype "passive"))
      (node (ref "C20") (pin "1") (pinfunction "1_1") (pintype "passive"))
      (node (ref "C21") (pin "1") (pinfunction "1_1") (pintype "passive"))
      (node (ref "C22") (pin "1") (pinfunction "1_1") (pintype "passive"))
      (node (ref "C23") (pin "1") (pinfunction "1_1") (pintype "passive"))
      (node (ref "C24") (pin "1") (pinfunction "1_1") (pintype "passive"))
      (node (ref "C25") (pin "1") (pinfunction "1_1") (pintype "passive"))
      (node (ref "C26") (pin "2") (pinfunction "2_2") (pintype "passive"))
      (node (ref "C27") (pin "1") (pinfunction "1_1") (pintype "passive"))
      (node (ref "C28") (pin "2") (pinfunction "2_2") (pintype "passive"))
      (node (ref "C29") (pin "2") (pinfunction "2_2") (pintype "passive"))
      (node (ref "C3") (pin "2") (pinfunction "2_2") (pintype "passive"))
      (node (ref "C30") (pin "2") (pinfunction "2_2") (pintype "passive"))
      (node (ref "C31") (pin "2") (pinfunction "2_2") (pintype "passive"))
      (node (ref "C32") (pin "1") (pinfunction "1_1") (pintype "passive"))
      (node (ref "C33") (pin "1") (pinfunction "1_1") (pintype "passive"))
      (node (ref "C4") (pin "2") (pinfunction "2_2") (pintype "passive"))
      (node (ref "C9") (pin "1") (pinfunction "1_1") (pintype "passive"))
      (node (ref "CVBS") (pin "GND") (pinfunction "GND_GND") (pintype "passive"))
      (node (ref "D1") (pin "A") (pinfunction "A_A") (pintype "passive"))
      (node (ref "D2") (pin "C") (pinfunction "C_C") (pintype "passive"))
      (node (ref "D3") (pin "C") (pinfunction "C_C") (pintype "passive"))
      (node (ref "D4") (pin "C") (pinfunction "C_C") (pintype "passive"))
      (node (ref "D5") (pin "C") (pinfunction "C_C") (pintype "passive"))
      (node (ref "EAR") (pin "SLEEVE") (pinfunction "SLEEVE_SLEEVE") (pintype "bidirectional"))
      (node (ref "J10") (pin "12") (pinfunction "12_12") (pintype "passive"))
      (node (ref "J11") (pin "12") (pinfunction "12_12") (pintype "passive"))
      (node (ref "JOY") (pin "8") (pinfunction "8_8") (pintype "passive"))
      (node (ref "JTAG") (pin "2") (pinfunction "S_2") (pintype "passive"))
      (node (ref "PS/2") (pin "3") (pinfunction "3_3") (pintype "passive"))
      (node (ref "PWCON") (pin "1") (pinfunction "1_1") (pintype "passive"))
      (node (ref "PWUSB") (pin "5") (pinfunction "GND_5") (pintype "bidirectional"))
      (node (ref "R1") (pin "2") (pinfunction "2_2") (pintype "passive"))
      (node (ref "R2") (pin "2") (pinfunction "2_2") (pintype "passive"))
      (node (ref "R29") (pin "2") (pinfunction "2_2") (pintype "passive"))
      (node (ref "R3") (pin "2") (pinfunction "2_2") (pintype "passive"))
      (node (ref "RGB") (pin "1") (pinfunction "S_1") (pintype "passive"))
      (node (ref "RST") (pin "1") (pinfunction "1_1") (pintype "passive"))
      (node (ref "SDCARD") (pin "3") (pinfunction "VSS1_3") (pintype "power_in"))
      (node (ref "SDCARD") (pin "6") (pinfunction "VSS2_6") (pintype "power_in"))
      (node (ref "SDCARD") (pin "M1") (pinfunction "GND_M1") (pintype "power_in"))
      (node (ref "SDCARD") (pin "M2") (pinfunction "GND_M2") (pintype "power_in"))
      (node (ref "SDCARD") (pin "M3") (pinfunction "GND_M3") (pintype "power_in"))
      (node (ref "SDCARD") (pin "M4") (pinfunction "GND_M4") (pintype "power_in"))
      (node (ref "T1") (pin "2") (pinfunction "E_2") (pintype "passive"))
      (node (ref "U1") (pin "P108") (pinfunction "GND_P108") (pintype "power_in"))
      (node (ref "U1") (pin "P113") (pinfunction "GND_P113") (pintype "power_in"))
      (node (ref "U1") (pin "P13") (pinfunction "GND_P13") (pintype "power_in"))
      (node (ref "U1") (pin "P130") (pinfunction "GND_P130") (pintype "power_in"))
      (node (ref "U1") (pin "P136") (pinfunction "GND_P136") (pintype "power_in"))
      (node (ref "U1") (pin "P144") (pinfunction "IO_L1P_HSWAPEN_0_P144") (pintype "bidirectional"))
      (node (ref "U1") (pin "P25") (pinfunction "GND_P25") (pintype "power_in"))
      (node (ref "U1") (pin "P3") (pinfunction "GND_P3") (pintype "power_in"))
      (node (ref "U1") (pin "P49") (pinfunction "GND_P49") (pintype "power_in"))
      (node (ref "U1") (pin "P54") (pinfunction "GND_P54") (pintype "power_in"))
      (node (ref "U1") (pin "P60") (pinfunction "IO_L13P_M1_2_P60") (pintype "bidirectional"))
      (node (ref "U1") (pin "P68") (pinfunction "GND_P68") (pintype "power_in"))
      (node (ref "U1") (pin "P73") (pinfunction "SUSPEND_P73") (pintype "input"))
      (node (ref "U1") (pin "P77") (pinfunction "GND_P77") (pintype "power_in"))
      (node (ref "U1") (pin "P91") (pinfunction "GND_P91") (pintype "power_in"))
      (node (ref "U1") (pin "P96") (pinfunction "GND_P96") (pintype "power_in"))
      (node (ref "U2") (pin "4") (pinfunction "GND_4") (pintype "bidirectional"))
      (node (ref "U3") (pin "12") (pinfunction "VSS_12") (pintype "input"))
      (node (ref "U3") (pin "34") (pinfunction "VSS_34") (pintype "input"))
      (node (ref "U3") (pin "37") (pinfunction "~{OE}_37") (pintype "input"))
      (node (ref "U3") (pin "8") (pinfunction "~{CS}_8") (pintype "input"))
      (node (ref "U4") (pin "12") (pinfunction "YTRAP_12") (pintype "bidirectional"))
      (node (ref "U4") (pin "13") (pinfunction "DGND_13") (pintype "bidirectional"))
      (node (ref "U4") (pin "2") (pinfunction "AGND_2") (pintype "bidirectional"))
      (node (ref "U5") (pin "2") (pinfunction "GND_2") (pintype "power_in"))
      (node (ref "U6") (pin "1") (pinfunction "GND_1") (pintype "power_in"))
      (node (ref "U7") (pin "1") (pinfunction "GND_1") (pintype "power_in"))
    )
    (net (code "115") (name "Net-(C2-Pad1)") (class "Default")
      (node (ref "C2") (pin "1") (pinfunction "1_1") (pintype "passive"))
      (node (ref "C5") (pin "1") (pinfunction "1_1") (pintype "passive"))
      (node (ref "D1") (pin "C") (pinfunction "C_C") (pintype "passive"))
      (node (ref "R28") (pin "1") (pinfunction "1_1") (pintype "passive"))
    )
    (net (code "116") (name "Net-(C3-Pad1)") (class "Default")
      (node (ref "C3") (pin "1") (pinfunction "1_1") (pintype "passive"))
      (node (ref "C35") (pin "1") (pinfunction "1_1") (pintype "passive"))
      (node (ref "R23") (pin "1") (pinfunction "1_1") (pintype "passive"))
    )
    (net (code "117") (name "Net-(C5-Pad2)") (class "Default")
      (node (ref "C5") (pin "2") (pinfunction "2_2") (pintype "passive"))
      (node (ref "R15") (pin "2") (pinfunction "2_2") (pintype "passive"))
    )
    (net (code "118") (name "Net-(C34-Pad1)") (class "Default")
      (node (ref "C34") (pin "1") (pinfunction "1_1") (pintype "passive"))
      (node (ref "C4") (pin "1") (pinfunction "1_1") (pintype "passive"))
      (node (ref "R22") (pin "1") (pinfunction "1_1") (pintype "passive"))
    )
    (net (code "119") (name "Net-(C36-Pad-)") (class "Default")
      (node (ref "C36") (pin "-") (pinfunction "-_-") (pintype "passive"))
      (node (ref "R4") (pin "1") (pinfunction "1_1") (pintype "passive"))
    )
    (net (code "120") (name "Net-(CVBS-PadSIG)") (class "Default")
      (node (ref "CVBS") (pin "SIG") (pinfunction "SIG_SIG") (pintype "passive"))
      (node (ref "R4") (pin "2") (pinfunction "2_2") (pintype "passive"))
    )
    (net (code "121") (name "Net-(D2-PadA)") (class "Default")
      (node (ref "D2") (pin "A") (pinfunction "A_A") (pintype "passive"))
      (node (ref "R25") (pin "2") (pinfunction "2_2") (pintype "passive"))
      (node (ref "Y1") (pin "1") (pinfunction "1_1") (pintype "passive"))
    )
    (net (code "122") (name "Net-(D3-PadA)") (class "Default")
      (node (ref "D3") (pin "A") (pinfunction "A_A") (pintype "passive"))
      (node (ref "R26") (pin "1") (pinfunction "1_1") (pintype "passive"))
      (node (ref "Y2") (pin "1") (pinfunction "1_1") (pintype "passive"))
    )
    (net (code "123") (name "Net-(D4-PadA)") (class "Default")
      (node (ref "D4") (pin "A") (pinfunction "A_A") (pintype "passive"))
      (node (ref "R6") (pin "1") (pinfunction "1_1") (pintype "passive"))
    )
    (net (code "124") (name "Net-(D5-PadA)") (class "Default")
      (node (ref "D5") (pin "A") (pinfunction "A_A") (pintype "passive"))
      (node (ref "R7") (pin "1") (pinfunction "1_1") (pintype "passive"))
    )
    (net (code "125") (name "Net-(EAR-LEFT)") (class "Default")
      (node (ref "EAR") (pin "TIP") (pinfunction "LEFT_TIP") (pintype "bidirectional"))
      (node (ref "R15") (pin "1") (pinfunction "1_1") (pintype "passive"))
      (node (ref "R29") (pin "1") (pinfunction "1_1") (pintype "passive"))
    )
    (net (code "126") (name "Net-(J16-Pad4)") (class "Default")
      (node (ref "J16") (pin "4") (pinfunction "4_4") (pintype "passive"))
      (node (ref "R5") (pin "2") (pinfunction "2_2") (pintype "passive"))
    )
    (net (code "127") (name "Net-(L3-Pad1)") (class "Default")
      (node (ref "L3") (pin "1") (pinfunction "1_1") (pintype "passive"))
      (node (ref "PWSW") (pin "1") (pinfunction "1_1") (pintype "passive"))
    )
    (net (code "128") (name "Net-(PS/2-Pad1)") (class "Default")
      (node (ref "PS/2") (pin "1") (pinfunction "1_1") (pintype "passive"))
      (node (ref "R8") (pin "1") (pinfunction "1_1") (pintype "passive"))
    )
    (net (code "129") (name "Net-(PS/2-Pad2)") (class "Default")
      (node (ref "PS/2") (pin "2") (pinfunction "2_2") (pintype "passive"))
      (node (ref "R9") (pin "1") (pinfunction "1_1") (pintype "passive"))
    )
    (net (code "130") (name "Net-(PS/2-Pad5)") (class "Default")
      (node (ref "PS/2") (pin "5") (pinfunction "5_5") (pintype "passive"))
      (node (ref "R10") (pin "1") (pinfunction "1_1") (pintype "passive"))
    )
    (net (code "131") (name "Net-(PS/2-Pad6)") (class "Default")
      (node (ref "PS/2") (pin "6") (pinfunction "6_6") (pintype "passive"))
      (node (ref "R11") (pin "1") (pinfunction "1_1") (pintype "passive"))
    )
    (net (code "132") (name "Net-(PWUSB-VCC)") (class "Default")
      (node (ref "PWCON") (pin "2") (pinfunction "2_2") (pintype "passive"))
      (node (ref "PWSW") (pin "2") (pinfunction "2_2") (pintype "passive"))
      (node (ref "PWUSB") (pin "1") (pinfunction "VCC_1") (pintype "bidirectional"))
    )
    (net (code "133") (name "Net-(SDCARD-DAT1)") (class "Default")
      (node (ref "R31") (pin "1") (pinfunction "1_1") (pintype "passive"))
      (node (ref "SDCARD") (pin "8") (pinfunction "DAT1_8") (pintype "bidirectional"))
    )
    (net (code "134") (name "Net-(SDCARD-DAT2)") (class "Default")
      (node (ref "R32") (pin "1") (pinfunction "1_1") (pintype "passive"))
      (node (ref "SDCARD") (pin "9") (pinfunction "DAT2_9") (pintype "bidirectional"))
    )
    (net (code "135") (name "Net-(T1-B)") (class "Default")
      (node (ref "R28") (pin "2") (pinfunction "2_2") (pintype "passive"))
      (node (ref "T1") (pin "1") (pinfunction "B_1") (pintype "passive"))
    )
    (net (code "136") (name "Net-(U1C-PROGRAM_B_2)") (class "Default")
      (node (ref "R24") (pin "1") (pinfunction "1_1") (pintype "passive"))
      (node (ref "RST") (pin "2") (pinfunction "2_2") (pintype "passive"))
      (node (ref "U1") (pin "P37") (pinfunction "PROGRAM_B_2_P37") (pintype "input"))
    )
    (net (code "137") (name "Net-(U4-4FSC)") (class "Default")
      (node (ref "C1") (pin "1") (pinfunction "1_1") (pintype "passive"))
      (node (ref "U4") (pin "3") (pinfunction "4FSC_3") (pintype "bidirectional"))
      (node (ref "Y1") (pin "2") (pinfunction "2_2") (pintype "passive"))
      (node (ref "Y2") (pin "2") (pinfunction "2_2") (pintype "passive"))
    )
    (net (code "138") (name "Net-(U4-BIN)") (class "Default")
      (node (ref "C8") (pin "1") (pinfunction "1_1") (pintype "passive"))
      (node (ref "U4") (pin "8") (pinfunction "BIN_8") (pintype "bidirectional"))
    )
    (net (code "139") (name "Net-(U4-COMP)") (class "Default")
      (node (ref "C36") (pin "+") (pinfunction "+_+") (pintype "passive"))
      (node (ref "U4") (pin "10") (pinfunction "COMP_10") (pintype "bidirectional"))
    )
    (net (code "140") (name "Net-(U4-GIN)") (class "Default")
      (node (ref "C7") (pin "1") (pinfunction "1_1") (pintype "passive"))
      (node (ref "U4") (pin "7") (pinfunction "GIN_7") (pintype "bidirectional"))
    )
    (net (code "141") (name "Net-(U4-RIN)") (class "Default")
      (node (ref "C6") (pin "1") (pinfunction "1_1") (pintype "passive"))
      (node (ref "U4") (pin "6") (pinfunction "RIN_6") (pintype "bidirectional"))
    )
    (net (code "142") (name "Net-(U6-VOUT)") (class "Default")
      (node (ref "C29") (pin "1") (pinfunction "1_1") (pintype "passive"))
      (node (ref "L1") (pin "1") (pinfunction "1_1") (pintype "passive"))
      (node (ref "U6") (pin "2") (pinfunction "VOUT_2") (pintype "output"))
    )
    (net (code "143") (name "Net-(U7-VOUT)") (class "Default")
      (node (ref "C31") (pin "1") (pinfunction "1_1") (pintype "passive"))
      (node (ref "L2") (pin "1") (pinfunction "1_1") (pintype "passive"))
      (node (ref "U7") (pin "2") (pinfunction "VOUT_2") (pintype "output"))
    )
    (net (code "144") (name "unconnected-(EAR-RIGHT-PadRING)") (class "Default")
      (node (ref "EAR") (pin "RING") (pinfunction "RIGHT_RING") (pintype "bidirectional"))
    )
    (net (code "145") (name "unconnected-(J10-Pad11)") (class "Default")
      (node (ref "J10") (pin "11") (pinfunction "11_11") (pintype "passive"))
    )
    (net (code "146") (name "unconnected-(PWUSB-D+-Pad3)") (class "Default")
      (node (ref "PWUSB") (pin "3") (pinfunction "D+_3") (pintype "bidirectional"))
    )
    (net (code "147") (name "unconnected-(PWUSB-D--Pad2)") (class "Default")
      (node (ref "PWUSB") (pin "2") (pinfunction "D-_2") (pintype "bidirectional"))
    )
    (net (code "148") (name "unconnected-(PWUSB-ID-Pad4)") (class "Default")
      (node (ref "PWUSB") (pin "4") (pinfunction "ID_4") (pintype "bidirectional"))
    )
    (net (code "149") (name "unconnected-(PWUSB-SHIELD-Pad6)") (class "Default")
      (node (ref "PWUSB") (pin "6") (pinfunction "SHIELD_6") (pintype "bidirectional"))
    )
    (net (code "150") (name "unconnected-(SDCARD-CDI#-Pad10)") (class "Default")
      (node (ref "SDCARD") (pin "10") (pinfunction "CDI#_10") (pintype "output"))
    )
    (net (code "151") (name "unconnected-(SDCARD-WP-Pad11)") (class "Default")
      (node (ref "SDCARD") (pin "11") (pinfunction "WP_11") (pintype "output"))
    )
    (net (code "152") (name "unconnected-(U1C-CMPCS_B_2-PadP72)") (class "Default")
      (node (ref "U1") (pin "P72") (pinfunction "CMPCS_B_2_P72") (pintype "bidirectional"))
    )
    (net (code "153") (name "unconnected-(U1C-DONE_2-PadP71)") (class "Default")
      (node (ref "U1") (pin "P71") (pinfunction "DONE_2_P71") (pintype "bidirectional"))
    )
    (net (code "154") (name "unconnected-(U4-CRMA-Pad9)") (class "Default")
      (node (ref "U4") (pin "9") (pinfunction "CRMA_9") (pintype "bidirectional"))
    )
    (net (code "155") (name "unconnected-(U4-LUMA-Pad11)") (class "Default")
      (node (ref "U4") (pin "11") (pinfunction "LUMA_11") (pintype "bidirectional"))
    )
    (net (code "156") (name "unconnected-(U5-E{slash}D-Pad1)") (class "Default")
      (node (ref "U5") (pin "1") (pinfunction "E/D_1") (pintype "input"))
    )
  )
)
